# OMODRI_Power.net
KiCad netlist of a schematic drawn in Altium Designer
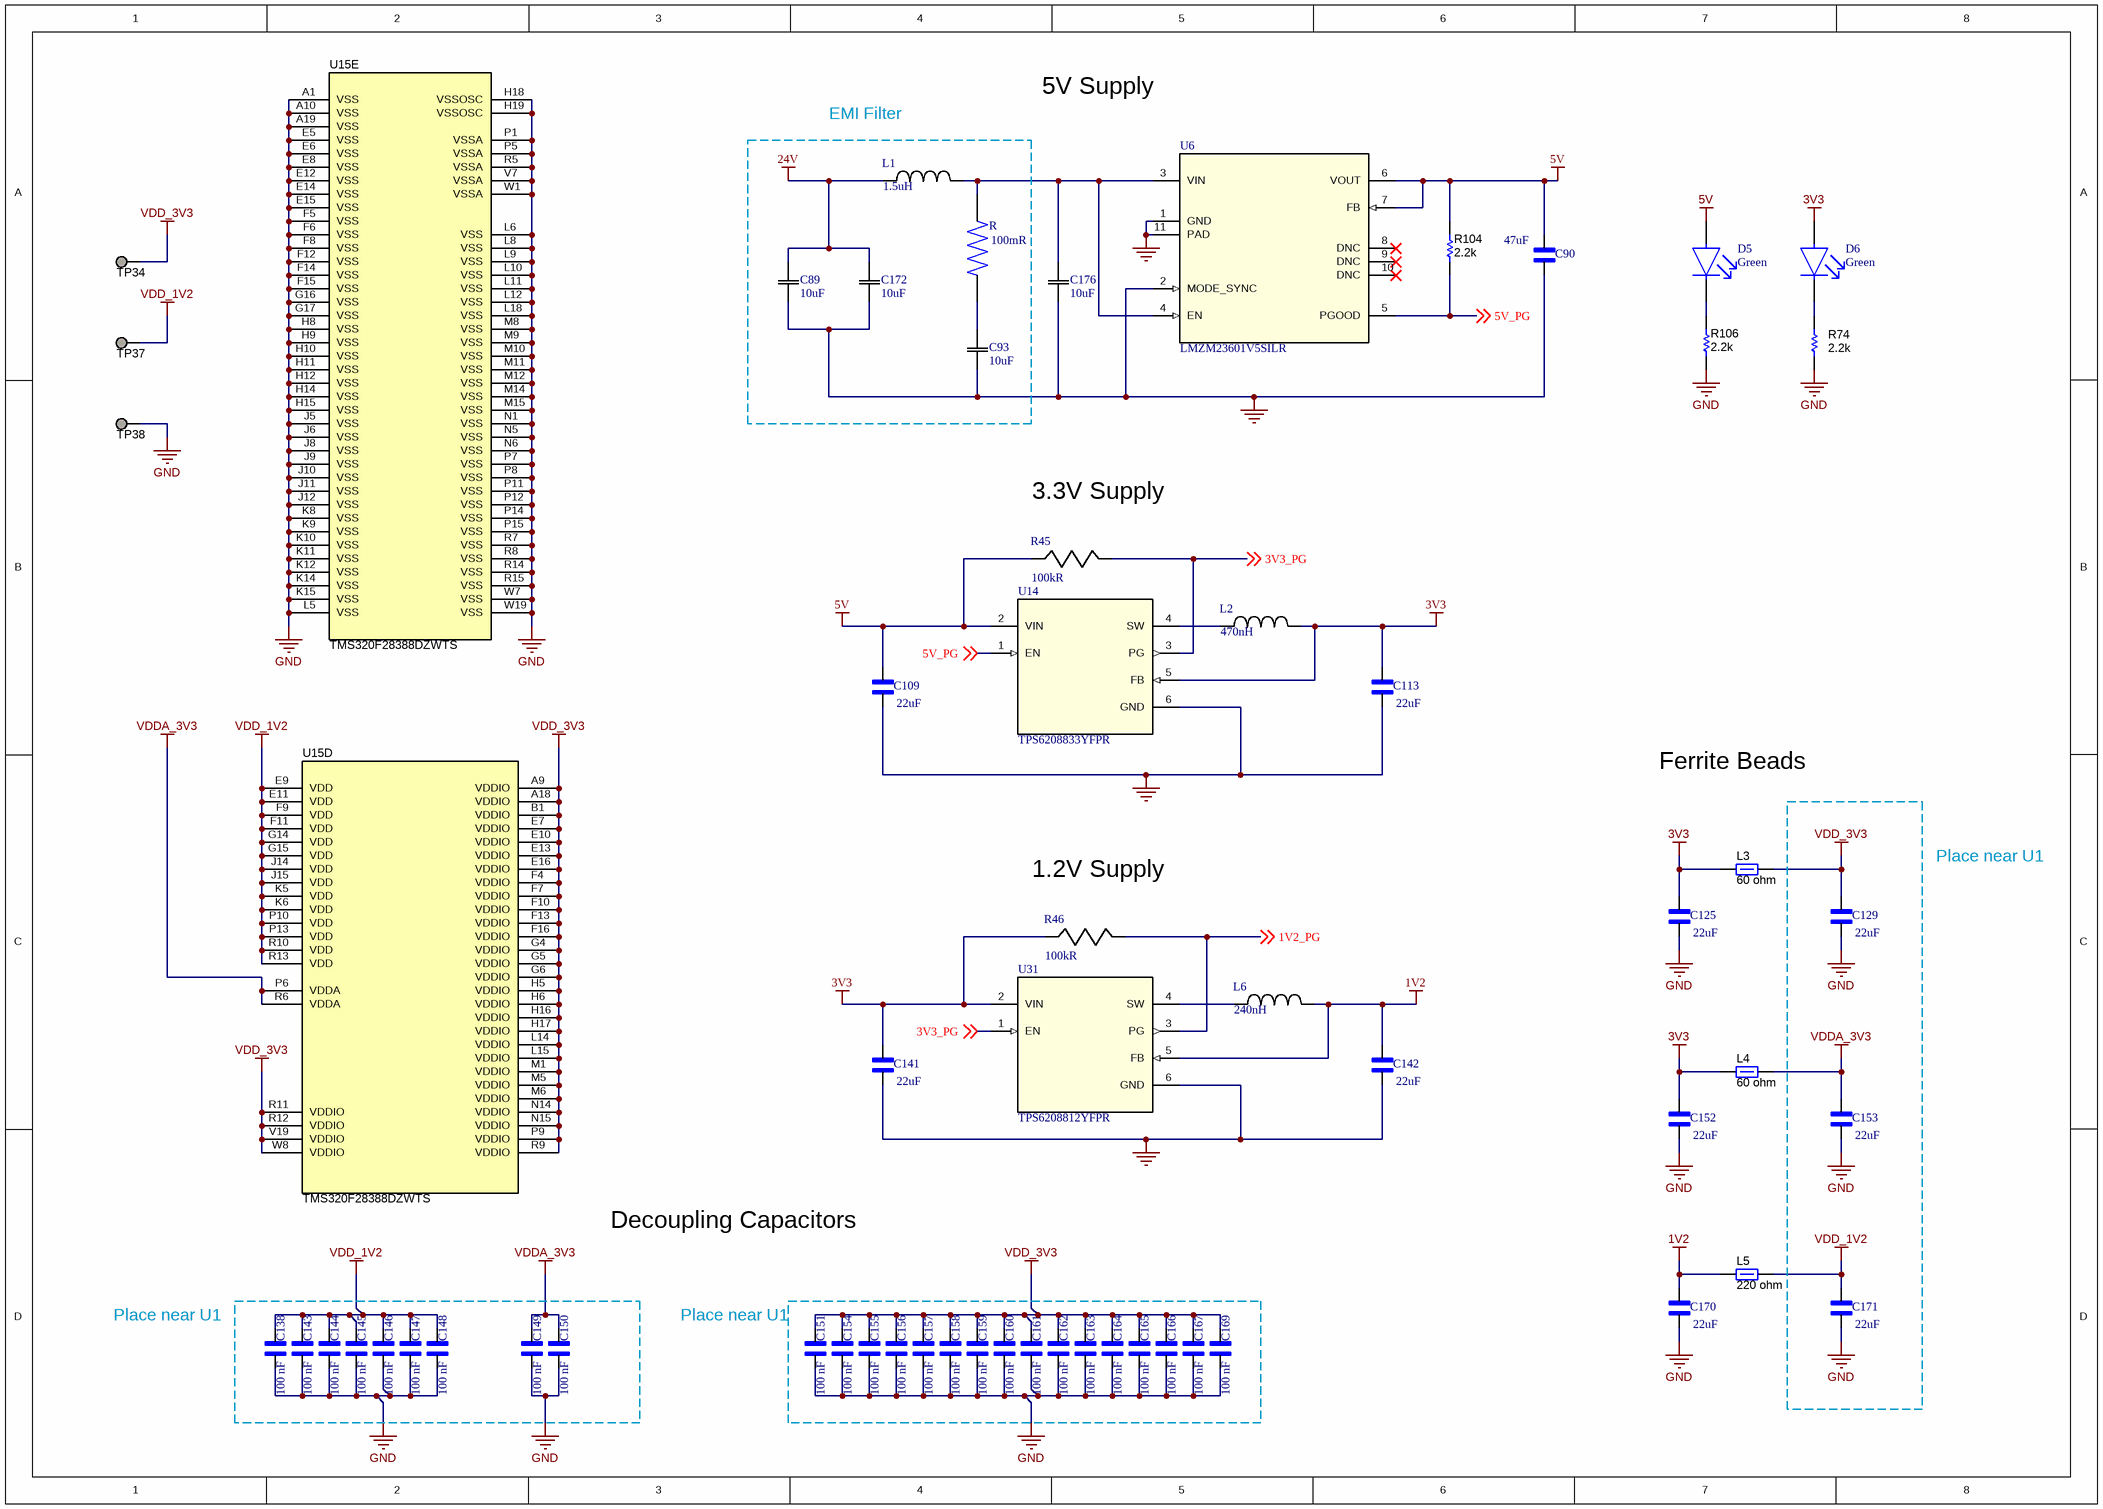
[diagram p0: OMODRI_Power.SchDoc]

(export (version "E")
  (design (tool "Eeschema 10.0.6"))
  (components
    (comp (ref "C89")
      (value "Part Number: CL10A106MA8NRNC")
      (footprint "CAP_CL10")
      (description "CAP CER 10UF 25V X5R 0603")
      (fields
        (field (name "MANUFACTURER_PART_NUMBER") "CL10A106MA8NRNC")
        (field (name "MANUFACTURER") "Samsung")
        (field (name "CAPACITANCE") "10uF")
        (field (name "COPYRIGHT") "Copyright (C) 2018 Accelerated Designs. All rights reserved")
      )
      (libsource (lib "Samsung-Capacitor") (part "CL10A106MA8NRNC"))
    )
    (comp (ref "C90")
      (value "47uF")
      (footprint "CAPC2012X145N")
      (description "47µF ±20% 10V Ceramic Capacitor X5R 0805 _2012 Metric_")
      (fields (field (name "MF") "TDK") (field (name "MP") "C2012X5R1A476M125AC"))
      (libsource (lib "C2012X5R1A476M125AC") (part "C2012X5R1A476M125AC"))
    )
    (comp (ref "C93")
      (value "Part Number: CL10A106MA8NRNC")
      (footprint "CAP_CL10")
      (description "CAP CER 10UF 25V X5R 0603")
      (fields
        (field (name "MANUFACTURER_PART_NUMBER") "CL10A106MA8NRNC")
        (field (name "MANUFACTURER") "Samsung")
        (field (name "CAPACITANCE") "10uF")
        (field (name "COPYRIGHT") "Copyright (C) 2018 Accelerated Designs. All rights reserved")
      )
      (libsource (lib "Samsung-Capacitor") (part "CL10A106MA8NRNC"))
    )
    (comp (ref "C109")
      (value "22uF")
      (footprint "CAPC1005X55N")
      (description "22µF ±20% 6.3V Ceramic Capacitor X5R 0402 (1005 Metric)")
      (fields (field (name "MP") "CL05A226MQ5N6J8") (field (name "MF") "Samsung Electro-Mechanics"))
      (libsource (lib "CL05A226MQ5N6J8") (part "CL05A226MQ5N6J8"))
    )
    (comp (ref "C113")
      (value "22uF")
      (footprint "CAPC1005X55N")
      (description "22µF ±20% 6.3V Ceramic Capacitor X5R 0402 (1005 Metric)")
      (fields (field (name "MP") "CL05A226MQ5N6J8") (field (name "MF") "Samsung Electro-Mechanics"))
      (libsource (lib "CL05A226MQ5N6J8") (part "CL05A226MQ5N6J8"))
    )
    (comp (ref "C125")
      (value "22uF")
      (footprint "CAPC1005X55N")
      (description "22µF ±20% 6.3V Ceramic Capacitor X5R 0402 (1005 Metric)")
      (fields (field (name "MP") "CL05A226MQ5N6J8") (field (name "MF") "Samsung Electro-Mechanics"))
      (libsource (lib "CL05A226MQ5N6J8") (part "CL05A226MQ5N6J8"))
    )
    (comp (ref "C129")
      (value "22uF")
      (footprint "CAPC1005X55N")
      (description "22µF ±20% 6.3V Ceramic Capacitor X5R 0402 (1005 Metric)")
      (fields (field (name "MP") "CL05A226MQ5N6J8") (field (name "MF") "Samsung Electro-Mechanics"))
      (libsource (lib "CL05A226MQ5N6J8") (part "CL05A226MQ5N6J8"))
    )
    (comp (ref "C138")
      (value "100 nF")
      (footprint "CAPC0603X33N")
      (description "SMD Capacitor X5R_EIA_ with Capacitance: 0.10uF Tol. 10%. Rated Voltage: 25Vdc")
      (fields (field (name "MF") "Murata") (field (name "MP") "GRM033R61E104KE14D"))
      (libsource (lib "GRM033R61E104KE14D") (part "GRM033R61E104KE14D"))
    )
    (comp (ref "C141")
      (value "22uF")
      (footprint "CAPC1005X55N")
      (description "22µF ±20% 6.3V Ceramic Capacitor X5R 0402 (1005 Metric)")
      (fields (field (name "MP") "CL05A226MQ5N6J8") (field (name "MF") "Samsung Electro-Mechanics"))
      (libsource (lib "CL05A226MQ5N6J8") (part "CL05A226MQ5N6J8"))
    )
    (comp (ref "C142")
      (value "22uF")
      (footprint "CAPC1005X55N")
      (description "22µF ±20% 6.3V Ceramic Capacitor X5R 0402 (1005 Metric)")
      (fields (field (name "MP") "CL05A226MQ5N6J8") (field (name "MF") "Samsung Electro-Mechanics"))
      (libsource (lib "CL05A226MQ5N6J8") (part "CL05A226MQ5N6J8"))
    )
    (comp (ref "C143")
      (value "100 nF")
      (footprint "CAPC0603X33N")
      (description "SMD Capacitor X5R_EIA_ with Capacitance: 0.10uF Tol. 10%. Rated Voltage: 25Vdc")
      (fields (field (name "MF") "Murata") (field (name "MP") "GRM033R61E104KE14D"))
      (libsource (lib "GRM033R61E104KE14D") (part "GRM033R61E104KE14D"))
    )
    (comp (ref "C144")
      (value "100 nF")
      (footprint "CAPC0603X33N")
      (description "SMD Capacitor X5R_EIA_ with Capacitance: 0.10uF Tol. 10%. Rated Voltage: 25Vdc")
      (fields (field (name "MF") "Murata") (field (name "MP") "GRM033R61E104KE14D"))
      (libsource (lib "GRM033R61E104KE14D") (part "GRM033R61E104KE14D"))
    )
    (comp (ref "C145")
      (value "100 nF")
      (footprint "CAPC0603X33N")
      (description "SMD Capacitor X5R_EIA_ with Capacitance: 0.10uF Tol. 10%. Rated Voltage: 25Vdc")
      (fields (field (name "MF") "Murata") (field (name "MP") "GRM033R61E104KE14D"))
      (libsource (lib "GRM033R61E104KE14D") (part "GRM033R61E104KE14D"))
    )
    (comp (ref "C146")
      (value "100 nF")
      (footprint "CAPC0603X33N")
      (description "SMD Capacitor X5R_EIA_ with Capacitance: 0.10uF Tol. 10%. Rated Voltage: 25Vdc")
      (fields (field (name "MF") "Murata") (field (name "MP") "GRM033R61E104KE14D"))
      (libsource (lib "GRM033R61E104KE14D") (part "GRM033R61E104KE14D"))
    )
    (comp (ref "C147")
      (value "100 nF")
      (footprint "CAPC0603X33N")
      (description "SMD Capacitor X5R_EIA_ with Capacitance: 0.10uF Tol. 10%. Rated Voltage: 25Vdc")
      (fields (field (name "MF") "Murata") (field (name "MP") "GRM033R61E104KE14D"))
      (libsource (lib "GRM033R61E104KE14D") (part "GRM033R61E104KE14D"))
    )
    (comp (ref "C148")
      (value "100 nF")
      (footprint "CAPC0603X33N")
      (description "SMD Capacitor X5R_EIA_ with Capacitance: 0.10uF Tol. 10%. Rated Voltage: 25Vdc")
      (fields (field (name "MF") "Murata") (field (name "MP") "GRM033R61E104KE14D"))
      (libsource (lib "GRM033R61E104KE14D") (part "GRM033R61E104KE14D"))
    )
    (comp (ref "C149")
      (value "100 nF")
      (footprint "CAPC0603X33N")
      (description "SMD Capacitor X5R_EIA_ with Capacitance: 0.10uF Tol. 10%. Rated Voltage: 25Vdc")
      (fields (field (name "MF") "Murata") (field (name "MP") "GRM033R61E104KE14D"))
      (libsource (lib "GRM033R61E104KE14D") (part "GRM033R61E104KE14D"))
    )
    (comp (ref "C150")
      (value "100 nF")
      (footprint "CAPC0603X33N")
      (description "SMD Capacitor X5R_EIA_ with Capacitance: 0.10uF Tol. 10%. Rated Voltage: 25Vdc")
      (fields (field (name "MF") "Murata") (field (name "MP") "GRM033R61E104KE14D"))
      (libsource (lib "GRM033R61E104KE14D") (part "GRM033R61E104KE14D"))
    )
    (comp (ref "C151")
      (value "100 nF")
      (footprint "CAPC0603X33N")
      (description "SMD Capacitor X5R_EIA_ with Capacitance: 0.10uF Tol. 10%. Rated Voltage: 25Vdc")
      (fields (field (name "MF") "Murata") (field (name "MP") "GRM033R61E104KE14D"))
      (libsource (lib "GRM033R61E104KE14D") (part "GRM033R61E104KE14D"))
    )
    (comp (ref "C152")
      (value "22uF")
      (footprint "CAPC1005X55N")
      (description "22µF ±20% 6.3V Ceramic Capacitor X5R 0402 (1005 Metric)")
      (fields (field (name "MP") "CL05A226MQ5N6J8") (field (name "MF") "Samsung Electro-Mechanics"))
      (libsource (lib "CL05A226MQ5N6J8") (part "CL05A226MQ5N6J8"))
    )
    (comp (ref "C153")
      (value "22uF")
      (footprint "CAPC1005X55N")
      (description "22µF ±20% 6.3V Ceramic Capacitor X5R 0402 (1005 Metric)")
      (fields (field (name "MP") "CL05A226MQ5N6J8") (field (name "MF") "Samsung Electro-Mechanics"))
      (libsource (lib "CL05A226MQ5N6J8") (part "CL05A226MQ5N6J8"))
    )
    (comp (ref "C154")
      (value "100 nF")
      (footprint "CAPC0603X33N")
      (description "SMD Capacitor X5R_EIA_ with Capacitance: 0.10uF Tol. 10%. Rated Voltage: 25Vdc")
      (fields (field (name "MF") "Murata") (field (name "MP") "GRM033R61E104KE14D"))
      (libsource (lib "GRM033R61E104KE14D") (part "GRM033R61E104KE14D"))
    )
    (comp (ref "C155")
      (value "100 nF")
      (footprint "CAPC0603X33N")
      (description "SMD Capacitor X5R_EIA_ with Capacitance: 0.10uF Tol. 10%. Rated Voltage: 25Vdc")
      (fields (field (name "MF") "Murata") (field (name "MP") "GRM033R61E104KE14D"))
      (libsource (lib "GRM033R61E104KE14D") (part "GRM033R61E104KE14D"))
    )
    (comp (ref "C156")
      (value "100 nF")
      (footprint "CAPC0603X33N")
      (description "SMD Capacitor X5R_EIA_ with Capacitance: 0.10uF Tol. 10%. Rated Voltage: 25Vdc")
      (fields (field (name "MF") "Murata") (field (name "MP") "GRM033R61E104KE14D"))
      (libsource (lib "GRM033R61E104KE14D") (part "GRM033R61E104KE14D"))
    )
    (comp (ref "C157")
      (value "100 nF")
      (footprint "CAPC0603X33N")
      (description "SMD Capacitor X5R_EIA_ with Capacitance: 0.10uF Tol. 10%. Rated Voltage: 25Vdc")
      (fields (field (name "MF") "Murata") (field (name "MP") "GRM033R61E104KE14D"))
      (libsource (lib "GRM033R61E104KE14D") (part "GRM033R61E104KE14D"))
    )
    (comp (ref "C158")
      (value "100 nF")
      (footprint "CAPC0603X33N")
      (description "SMD Capacitor X5R_EIA_ with Capacitance: 0.10uF Tol. 10%. Rated Voltage: 25Vdc")
      (fields (field (name "MF") "Murata") (field (name "MP") "GRM033R61E104KE14D"))
      (libsource (lib "GRM033R61E104KE14D") (part "GRM033R61E104KE14D"))
    )
    (comp (ref "C159")
      (value "100 nF")
      (footprint "CAPC0603X33N")
      (description "SMD Capacitor X5R_EIA_ with Capacitance: 0.10uF Tol. 10%. Rated Voltage: 25Vdc")
      (fields (field (name "MF") "Murata") (field (name "MP") "GRM033R61E104KE14D"))
      (libsource (lib "GRM033R61E104KE14D") (part "GRM033R61E104KE14D"))
    )
    (comp (ref "C160")
      (value "100 nF")
      (footprint "CAPC0603X33N")
      (description "SMD Capacitor X5R_EIA_ with Capacitance: 0.10uF Tol. 10%. Rated Voltage: 25Vdc")
      (fields (field (name "MF") "Murata") (field (name "MP") "GRM033R61E104KE14D"))
      (libsource (lib "GRM033R61E104KE14D") (part "GRM033R61E104KE14D"))
    )
    (comp (ref "C161")
      (value "100 nF")
      (footprint "CAPC0603X33N")
      (description "SMD Capacitor X5R_EIA_ with Capacitance: 0.10uF Tol. 10%. Rated Voltage: 25Vdc")
      (fields (field (name "MF") "Murata") (field (name "MP") "GRM033R61E104KE14D"))
      (libsource (lib "GRM033R61E104KE14D") (part "GRM033R61E104KE14D"))
    )
    (comp (ref "C162")
      (value "100 nF")
      (footprint "CAPC0603X33N")
      (description "SMD Capacitor X5R_EIA_ with Capacitance: 0.10uF Tol. 10%. Rated Voltage: 25Vdc")
      (fields (field (name "MF") "Murata") (field (name "MP") "GRM033R61E104KE14D"))
      (libsource (lib "GRM033R61E104KE14D") (part "GRM033R61E104KE14D"))
    )
    (comp (ref "C163")
      (value "100 nF")
      (footprint "CAPC0603X33N")
      (description "SMD Capacitor X5R_EIA_ with Capacitance: 0.10uF Tol. 10%. Rated Voltage: 25Vdc")
      (fields (field (name "MF") "Murata") (field (name "MP") "GRM033R61E104KE14D"))
      (libsource (lib "GRM033R61E104KE14D") (part "GRM033R61E104KE14D"))
    )
    (comp (ref "C164")
      (value "100 nF")
      (footprint "CAPC0603X33N")
      (description "SMD Capacitor X5R_EIA_ with Capacitance: 0.10uF Tol. 10%. Rated Voltage: 25Vdc")
      (fields (field (name "MF") "Murata") (field (name "MP") "GRM033R61E104KE14D"))
      (libsource (lib "GRM033R61E104KE14D") (part "GRM033R61E104KE14D"))
    )
    (comp (ref "C165")
      (value "100 nF")
      (footprint "CAPC0603X33N")
      (description "SMD Capacitor X5R_EIA_ with Capacitance: 0.10uF Tol. 10%. Rated Voltage: 25Vdc")
      (fields (field (name "MF") "Murata") (field (name "MP") "GRM033R61E104KE14D"))
      (libsource (lib "GRM033R61E104KE14D") (part "GRM033R61E104KE14D"))
    )
    (comp (ref "C166")
      (value "100 nF")
      (footprint "CAPC0603X33N")
      (description "SMD Capacitor X5R_EIA_ with Capacitance: 0.10uF Tol. 10%. Rated Voltage: 25Vdc")
      (fields (field (name "MF") "Murata") (field (name "MP") "GRM033R61E104KE14D"))
      (libsource (lib "GRM033R61E104KE14D") (part "GRM033R61E104KE14D"))
    )
    (comp (ref "C167")
      (value "100 nF")
      (footprint "CAPC0603X33N")
      (description "SMD Capacitor X5R_EIA_ with Capacitance: 0.10uF Tol. 10%. Rated Voltage: 25Vdc")
      (fields (field (name "MF") "Murata") (field (name "MP") "GRM033R61E104KE14D"))
      (libsource (lib "GRM033R61E104KE14D") (part "GRM033R61E104KE14D"))
    )
    (comp (ref "C169")
      (value "100 nF")
      (footprint "CAPC0603X33N")
      (description "SMD Capacitor X5R_EIA_ with Capacitance: 0.10uF Tol. 10%. Rated Voltage: 25Vdc")
      (fields (field (name "MF") "Murata") (field (name "MP") "GRM033R61E104KE14D"))
      (libsource (lib "GRM033R61E104KE14D") (part "GRM033R61E104KE14D"))
    )
    (comp (ref "C170")
      (value "22uF")
      (footprint "CAPC1005X55N")
      (description "22µF ±20% 6.3V Ceramic Capacitor X5R 0402 (1005 Metric)")
      (fields (field (name "MP") "CL05A226MQ5N6J8") (field (name "MF") "Samsung Electro-Mechanics"))
      (libsource (lib "CL05A226MQ5N6J8") (part "CL05A226MQ5N6J8"))
    )
    (comp (ref "C171")
      (value "22uF")
      (footprint "CAPC1005X55N")
      (description "22µF ±20% 6.3V Ceramic Capacitor X5R 0402 (1005 Metric)")
      (fields (field (name "MP") "CL05A226MQ5N6J8") (field (name "MF") "Samsung Electro-Mechanics"))
      (libsource (lib "CL05A226MQ5N6J8") (part "CL05A226MQ5N6J8"))
    )
    (comp (ref "C172")
      (value "Part Number: CL10A106MA8NRNC")
      (footprint "CAP_CL10")
      (description "CAP CER 10UF 25V X5R 0603")
      (fields
        (field (name "MANUFACTURER_PART_NUMBER") "CL10A106MA8NRNC")
        (field (name "MANUFACTURER") "Samsung")
        (field (name "CAPACITANCE") "10uF")
        (field (name "COPYRIGHT") "Copyright (C) 2018 Accelerated Designs. All rights reserved")
      )
      (libsource (lib "Samsung-Capacitor") (part "CL10A106MA8NRNC"))
    )
    (comp (ref "C176")
      (value "Part Number: CL10A106MA8NRNC")
      (footprint "CAP_CL10")
      (description "CAP CER 10UF 25V X5R 0603")
      (fields
        (field (name "MANUFACTURER_PART_NUMBER") "CL10A106MA8NRNC")
        (field (name "MANUFACTURER") "Samsung")
        (field (name "CAPACITANCE") "10uF")
        (field (name "COPYRIGHT") "Copyright (C) 2018 Accelerated Designs. All rights reserved")
      )
      (libsource (lib "Samsung-Capacitor") (part "CL10A106MA8NRNC"))
    )
    (comp (ref "D5")
      (value "SML-P11MTT86R")
      (footprint "ROHM-SML-P11MT_V")
      (description "LED Uni-Color Yellow Green 2-Pin Chip 0402(1006Metric) T/R")
      (fields
        (field (name "MANUFACTURER") "Rohm")
        (field (name "MANUFACTURER PART NUMBER") "SML-P11MTT86")
        (field (name "ILLUMINATION COLOR") "Green")
      )
      (libsource (lib "LED") (part "SML-P11MTT86R"))
    )
    (comp (ref "D6")
      (value "SML-P11MTT86R")
      (footprint "ROHM-SML-P11MT_V")
      (description "LED Uni-Color Yellow Green 2-Pin Chip 0402(1006Metric) T/R")
      (fields
        (field (name "MANUFACTURER") "Rohm")
        (field (name "MANUFACTURER PART NUMBER") "SML-P11MTT86")
        (field (name "ILLUMINATION COLOR") "Green")
      )
      (libsource (lib "LED") (part "SML-P11MTT86R"))
    )
    (comp (ref "L1")
      (value "LQM21PN1R5MC0D")
      (footprint "0805")
      (fields
        (field (name "MANUFACTURER") "Murata")
        (field (name "TOLERANCE") "20%")
        (field (name "INDUCTANCE") "1.5uH")
      )
      (libsource (lib "TI_LMZM23601V5") (part "LQM21PN1R5MC0D"))
    )
    (comp (ref "L2")
      (value "DFE18SANR47MG0L")
      (footprint "0603")
      (description "FIXED IND 470NH 2.6A 54 MOHM SMD")
      (fields
        (field (name "MANUFACTURER") "Murata")
        (field (name "TOLERANCE") "20%")
        (field (name "INDUCTANCE") "470nH")
      )
      (libsource (lib "TI_TPS_6208833") (part "DFE18SANR47MG0L"))
    )
    (comp (ref "L3")
      (value "60 ohm")
      (footprint "0805_HV")
      (description "Ferrite Bead, 60 ohm @ 100 MHz, 3 A, 0805")
      (fields
        (field (name "PARTNUMBER") "BKP2125HS600-T")
        (field (name "MANUFACTURER") "Taiyo Yuden")
        (field (name "PUBLISHER") "Texas Instruments")
      )
      (libsource (lib "Altium Vault - TI") (part "Ferrite_Bead"))
    )
    (comp (ref "L4")
      (value "60 ohm")
      (footprint "0805_HV")
      (description "Ferrite Bead, 60 ohm @ 100 MHz, 3 A, 0805")
      (fields
        (field (name "PARTNUMBER") "BKP2125HS600-T")
        (field (name "MANUFACTURER") "Taiyo Yuden")
        (field (name "PUBLISHER") "Texas Instruments")
      )
      (libsource (lib "Altium Vault - TI") (part "Ferrite_Bead"))
    )
    (comp (ref "L5")
      (value "220 ohm")
      (footprint "0805_HV")
      (description "Ferrite Bead, 220 ohm @ 100 MHz, 2 A, 0805")
      (fields
        (field (name "PARTNUMBER") "BLM21PG221SN1D")
        (field (name "MANUFACTURER") "MuRata")
        (field (name "PUBLISHER") "Texas Instruments")
      )
      (libsource (lib "Altium Vault - TI") (part "Ferrite_Bead"))
    )
    (comp (ref "L6")
      (value "DFE18SANR24ME0L")
      (footprint "DFE18_E")
      (description "FIXED IND 240NH 3.2A 36 MOHM SMD")
      (fields
        (field (name "MANUFACTURER") "Murata")
        (field (name "TOLERANCE") "20%")
        (field (name "INDUCTANCE") "240nH")
      )
      (libsource (lib "TI_TPS_6208812") (part "DFE18SANR24ME0L"))
    )
    (comp (ref "R")
      (value "100mR")
      (footprint "RESC0603X29N")
      (description "100 mOhms Â±1% 0.1W, 1/10W Chip Resistor 0201 (0603 Metric) Current Sense Thick Film")
      (fields (field (name "MF") "Rohm") (field (name "DIGI-KEY_PART_NUMBER") "RHM1694-1-ND"))
      (libsource (lib "UCR006YVPFLR100") (part "UCR006YVPFLR100"))
    )
    (comp (ref "R45")
      (value "CRCW0402100KFKED")
      (footprint "0402")
      (description "Res Thick Film 0402 100K Ohm 1% 1/16W 100ppm/C Molded SMD Paper T/R")
      (fields
        (field (name "MANUFACTURER") "Vishay")
        (field (name "TOLERANCE") "1%")
        (field (name "RESISTANCE") "100kR")
      )
      (libsource (lib "TI_TPS_6208833") (part "CRCW0402100KFKED"))
    )
    (comp (ref "R46")
      (value "CRCW0402100KFKED")
      (footprint "0402")
      (description "Res Thick Film 0402 100K Ohm 1% 1/16W 100ppm/C Molded SMD Paper T/R")
      (fields
        (field (name "MANUFACTURER") "Vishay")
        (field (name "TOLERANCE") "1%")
        (field (name "RESISTANCE") "100kR")
      )
      (libsource (lib "TI_TPS_6208833") (part "CRCW0402100KFKED"))
    )
    (comp (ref "R74")
      (value "CRCW04022K20JNED")
      (footprint "0402")
      (description "RES, 2.2 k, 5%, 0.063 W, AEC-Q200 Grade 0, 0402")
      (fields (field (name "MANUFACTURER") "Vishay-Dale") (field (name "VALUEDISPLAYED") "2.2k"))
      (libsource (lib "Altium Vault - TI") (part "Resistor"))
    )
    (comp (ref "R104")
      (value "CRCW04022K20JNED")
      (footprint "0402")
      (description "RES, 2.2 k, 5%, 0.063 W, AEC-Q200 Grade 0, 0402")
      (fields (field (name "MANUFACTURER") "Vishay-Dale") (field (name "VALUEDISPLAYED") "2.2k"))
      (libsource (lib "Altium Vault - TI") (part "Resistor"))
    )
    (comp (ref "R106")
      (value "CRCW04022K20JNED")
      (footprint "0402")
      (description "RES, 2.2 k, 5%, 0.063 W, AEC-Q200 Grade 0, 0402")
      (fields (field (name "MANUFACTURER") "Vishay-Dale") (field (name "VALUEDISPLAYED") "2.2k"))
      (libsource (lib "Altium Vault - TI") (part "Resistor"))
    )
    (comp (ref "TP34")
      (value "TESTPOINT")
      (footprint "TP_50MIL-25MILHOLE")
      (description "TEST POINT.  No entry in BOM.")
      (libsource (lib "Altium Vault - TI") (part "CMP-0078143-2"))
    )
    (comp (ref "TP37")
      (value "TESTPOINT")
      (footprint "TP_50MIL-25MILHOLE")
      (description "TEST POINT.  No entry in BOM.")
      (libsource (lib "Altium Vault - TI") (part "CMP-0078143-2"))
    )
    (comp (ref "TP38")
      (value "TESTPOINT")
      (footprint "TP_50MIL-25MILHOLE")
      (description "TEST POINT.  No entry in BOM.")
      (libsource (lib "Altium Vault - TI") (part "CMP-0078143-2"))
    )
    (comp (ref "U6")
      (value "LMZM23601V5SILR")
      (footprint "SIL0010A")
      (description "36-V, 1-A Step-Down DC-DC Power Module in 3.8-mm × 3-mm Package 10-uSiP -40 to 125")
      (fields (field (name "MANUFACTURER") "Texas Instruments"))
      (libsource (lib "TI_LMZM23601V5") (part "LMZM23601V5SILR"))
    )
    (comp (ref "U14")
      (value "TPS6208833YFPR")
      (footprint "YFP0006AAAA")
      (description "3A STEP-DOWN CONVERTER - FIXED 3")
      (fields (field (name "MANUFACTURER") "Texas Instruments"))
      (libsource (lib "TI_TPS_6208833") (part "TPS6208833YFPR"))
    )
    (comp (ref "U15")
      (value "TMS320F28388DZWTS")
      (footprint "ZWT0337A")
      (description "TMS320F28388DZWTS, ZWT0337A (NFBGA-337)")
      (fields
        (field (name "PARTNUMBER") "TMS320F28388DZWTS")
        (field (name "MANUFACTURER") "Texas Instruments")
      )
      (libsource (lib "Altium Vault - TI") (part "TMS320F28388"))
    )
    (comp (ref "U31")
      (value "TPS6208812YFPR")
      (footprint "YFP0006AAAA")
      (description "3A STEP-DOWN CONVERTER - FIXED 3")
      (fields (field (name "MANUFACTURER") "Texas Instruments"))
      (libsource (lib "TI_TPS_6208812") (part "TPS6208812YFPR"))
    )
  )
  (nets
    (net (code "1") (name "0") (class "Default")
      (node (ref "C109") (pin "1") (pinfunction "1_1") (pintype "passive"))
      (node (ref "C113") (pin "1") (pinfunction "1_1") (pintype "passive"))
      (node (ref "C141") (pin "1") (pinfunction "1_1") (pintype "passive"))
      (node (ref "C142") (pin "1") (pinfunction "1_1") (pintype "passive"))
      (node (ref "C172") (pin "1") (pinfunction "1_1") (pintype "passive"))
      (node (ref "C176") (pin "1") (pinfunction "1_1") (pintype "passive"))
      (node (ref "C89") (pin "1") (pinfunction "1_1") (pintype "passive"))
      (node (ref "C90") (pin "1") (pinfunction "1_1") (pintype "passive"))
      (node (ref "C93") (pin "1") (pinfunction "1_1") (pintype "passive"))
      (node (ref "U14") (pin "6") (pinfunction "GND_6") (pintype "power_in"))
      (node (ref "U31") (pin "6") (pinfunction "GND_6") (pintype "power_in"))
      (node (ref "U6") (pin "1") (pinfunction "GND_1") (pintype "power_in"))
      (node (ref "U6") (pin "11") (pinfunction "PAD_11") (pintype "power_in"))
      (node (ref "U6") (pin "2") (pinfunction "MODE_SYNC_2") (pintype "input"))
    )
    (net (code "2") (name "1V2") (class "Default")
      (node (ref "C142") (pin "2") (pinfunction "2_2") (pintype "passive"))
      (node (ref "C170") (pin "2") (pinfunction "2_2") (pintype "passive"))
      (node (ref "L5") (pin "1") (pinfunction "1_1") (pintype "passive"))
      (node (ref "L6") (pin "1") (pinfunction "1_1") (pintype "passive"))
      (node (ref "U31") (pin "5") (pinfunction "FB_5") (pintype "input"))
    )
    (net (code "3") (name "1V2_PG") (class "Default")
      (node (ref "R46") (pin "1") (pinfunction "1_1") (pintype "passive"))
      (node (ref "U31") (pin "3") (pinfunction "PG_3") (pintype "output"))
    )
    (net (code "4") (name "3V3") (class "Default")
      (node (ref "C113") (pin "2") (pinfunction "2_2") (pintype "passive"))
      (node (ref "C125") (pin "2") (pinfunction "2_2") (pintype "passive"))
      (node (ref "C141") (pin "2") (pinfunction "2_2") (pintype "passive"))
      (node (ref "C152") (pin "2") (pinfunction "2_2") (pintype "passive"))
      (node (ref "D6") (pin "2") (pinfunction "A_2") (pintype "passive"))
      (node (ref "L2") (pin "1") (pinfunction "1_1") (pintype "passive"))
      (node (ref "L3") (pin "1") (pinfunction "1_1") (pintype "passive"))
      (node (ref "L4") (pin "1") (pinfunction "1_1") (pintype "passive"))
      (node (ref "R46") (pin "2") (pinfunction "2_2") (pintype "passive"))
      (node (ref "U14") (pin "5") (pinfunction "FB_5") (pintype "input"))
      (node (ref "U31") (pin "2") (pinfunction "VIN_2") (pintype "power_in"))
    )
    (net (code "5") (name "3V3_PG") (class "Default")
      (node (ref "R45") (pin "1") (pinfunction "1_1") (pintype "passive"))
      (node (ref "U14") (pin "3") (pinfunction "PG_3") (pintype "output"))
      (node (ref "U31") (pin "1") (pinfunction "EN_1") (pintype "input"))
    )
    (net (code "6") (name "5V") (class "Default")
      (node (ref "C109") (pin "2") (pinfunction "2_2") (pintype "passive"))
      (node (ref "C90") (pin "2") (pinfunction "2_2") (pintype "passive"))
      (node (ref "D5") (pin "2") (pinfunction "A_2") (pintype "passive"))
      (node (ref "R104") (pin "1") (pinfunction "1_1") (pintype "passive"))
      (node (ref "R45") (pin "2") (pinfunction "2_2") (pintype "passive"))
      (node (ref "U14") (pin "2") (pinfunction "VIN_2") (pintype "power_in"))
      (node (ref "U6") (pin "6") (pinfunction "VOUT_6") (pintype "power_in"))
      (node (ref "U6") (pin "7") (pinfunction "FB_7") (pintype "input"))
    )
    (net (code "7") (name "5V_PG") (class "Default")
      (node (ref "R104") (pin "2") (pinfunction "2_2") (pintype "passive"))
      (node (ref "U14") (pin "1") (pinfunction "EN_1") (pintype "input"))
      (node (ref "U6") (pin "5") (pinfunction "PGOOD_5") (pintype "open_collector"))
    )
    (net (code "8") (name "24V") (class "Default")
      (node (ref "C172") (pin "2") (pinfunction "2_2") (pintype "passive"))
      (node (ref "C89") (pin "2") (pinfunction "2_2") (pintype "passive"))
      (node (ref "L1") (pin "1") (pinfunction "1_1") (pintype "passive"))
    )
    (net (code "9") (name "GND") (class "Default")
      (node (ref "C125") (pin "1") (pinfunction "1_1") (pintype "passive"))
      (node (ref "C129") (pin "1") (pinfunction "1_1") (pintype "passive"))
      (node (ref "C138") (pin "2") (pinfunction "2_2") (pintype "passive"))
      (node (ref "C143") (pin "2") (pinfunction "2_2") (pintype "passive"))
      (node (ref "C144") (pin "2") (pinfunction "2_2") (pintype "passive"))
      (node (ref "C145") (pin "2") (pinfunction "2_2") (pintype "passive"))
      (node (ref "C146") (pin "2") (pinfunction "2_2") (pintype "passive"))
      (node (ref "C147") (pin "2") (pinfunction "2_2") (pintype "passive"))
      (node (ref "C148") (pin "2") (pinfunction "2_2") (pintype "passive"))
      (node (ref "C149") (pin "2") (pinfunction "2_2") (pintype "passive"))
      (node (ref "C150") (pin "2") (pinfunction "2_2") (pintype "passive"))
      (node (ref "C151") (pin "2") (pinfunction "2_2") (pintype "passive"))
      (node (ref "C152") (pin "1") (pinfunction "1_1") (pintype "passive"))
      (node (ref "C153") (pin "1") (pinfunction "1_1") (pintype "passive"))
      (node (ref "C154") (pin "2") (pinfunction "2_2") (pintype "passive"))
      (node (ref "C155") (pin "2") (pinfunction "2_2") (pintype "passive"))
      (node (ref "C156") (pin "2") (pinfunction "2_2") (pintype "passive"))
      (node (ref "C157") (pin "2") (pinfunction "2_2") (pintype "passive"))
      (node (ref "C158") (pin "2") (pinfunction "2_2") (pintype "passive"))
      (node (ref "C159") (pin "2") (pinfunction "2_2") (pintype "passive"))
      (node (ref "C160") (pin "2") (pinfunction "2_2") (pintype "passive"))
      (node (ref "C161") (pin "2") (pinfunction "2_2") (pintype "passive"))
      (node (ref "C162") (pin "2") (pinfunction "2_2") (pintype "passive"))
      (node (ref "C163") (pin "2") (pinfunction "2_2") (pintype "passive"))
      (node (ref "C164") (pin "2") (pinfunction "2_2") (pintype "passive"))
      (node (ref "C165") (pin "2") (pinfunction "2_2") (pintype "passive"))
      (node (ref "C166") (pin "2") (pinfunction "2_2") (pintype "passive"))
      (node (ref "C167") (pin "2") (pinfunction "2_2") (pintype "passive"))
      (node (ref "C169") (pin "2") (pinfunction "2_2") (pintype "passive"))
      (node (ref "C170") (pin "1") (pinfunction "1_1") (pintype "passive"))
      (node (ref "C171") (pin "1") (pinfunction "1_1") (pintype "passive"))
      (node (ref "R106") (pin "2") (pinfunction "2_2") (pintype "passive"))
      (node (ref "R74") (pin "1") (pinfunction "1_1") (pintype "passive"))
      (node (ref "TP38") (pin "1") (pintype "passive"))
      (node (ref "U15") (pin "A1") (pinfunction "VSS_A1") (pintype "power_in"))
      (node (ref "U15") (pin "A10") (pinfunction "VSS_A10") (pintype "power_in"))
      (node (ref "U15") (pin "A19") (pinfunction "VSS_A19") (pintype "power_in"))
      (node (ref "U15") (pin "E12") (pinfunction "VSS_E12") (pintype "power_in"))
      (node (ref "U15") (pin "E14") (pinfunction "VSS_E14") (pintype "power_in"))
      (node (ref "U15") (pin "E15") (pinfunction "VSS_E15") (pintype "power_in"))
      (node (ref "U15") (pin "E5") (pinfunction "VSS_E5") (pintype "power_in"))
      (node (ref "U15") (pin "E6") (pinfunction "VSS_E6") (pintype "power_in"))
      (node (ref "U15") (pin "E8") (pinfunction "VSS_E8") (pintype "power_in"))
      (node (ref "U15") (pin "F12") (pinfunction "VSS_F12") (pintype "power_in"))
      (node (ref "U15") (pin "F14") (pinfunction "VSS_F14") (pintype "power_in"))
      (node (ref "U15") (pin "F15") (pinfunction "VSS_F15") (pintype "power_in"))
      (node (ref "U15") (pin "F5") (pinfunction "VSS_F5") (pintype "power_in"))
      (node (ref "U15") (pin "F6") (pinfunction "VSS_F6") (pintype "power_in"))
      (node (ref "U15") (pin "F8") (pinfunction "VSS_F8") (pintype "power_in"))
      (node (ref "U15") (pin "G16") (pinfunction "VSS_G16") (pintype "power_in"))
      (node (ref "U15") (pin "G17") (pinfunction "VSS_G17") (pintype "power_in"))
      (node (ref "U15") (pin "H10") (pinfunction "VSS_H10") (pintype "power_in"))
      (node (ref "U15") (pin "H11") (pinfunction "VSS_H11") (pintype "power_in"))
      (node (ref "U15") (pin "H12") (pinfunction "VSS_H12") (pintype "power_in"))
      (node (ref "U15") (pin "H14") (pinfunction "VSS_H14") (pintype "power_in"))
      (node (ref "U15") (pin "H15") (pinfunction "VSS_H15") (pintype "power_in"))
      (node (ref "U15") (pin "H18") (pinfunction "VSSOSC_H18") (pintype "power_in"))
      (node (ref "U15") (pin "H19") (pinfunction "VSSOSC_H19") (pintype "power_in"))
      (node (ref "U15") (pin "H8") (pinfunction "VSS_H8") (pintype "power_in"))
      (node (ref "U15") (pin "H9") (pinfunction "VSS_H9") (pintype "power_in"))
      (node (ref "U15") (pin "J10") (pinfunction "VSS_J10") (pintype "power_in"))
      (node (ref "U15") (pin "J11") (pinfunction "VSS_J11") (pintype "power_in"))
      (node (ref "U15") (pin "J12") (pinfunction "VSS_J12") (pintype "power_in"))
      (node (ref "U15") (pin "J5") (pinfunction "VSS_J5") (pintype "power_in"))
      (node (ref "U15") (pin "J6") (pinfunction "VSS_J6") (pintype "power_in"))
      (node (ref "U15") (pin "J8") (pinfunction "VSS_J8") (pintype "power_in"))
      (node (ref "U15") (pin "J9") (pinfunction "VSS_J9") (pintype "power_in"))
      (node (ref "U15") (pin "K10") (pinfunction "VSS_K10") (pintype "power_in"))
      (node (ref "U15") (pin "K11") (pinfunction "VSS_K11") (pintype "power_in"))
      (node (ref "U15") (pin "K12") (pinfunction "VSS_K12") (pintype "power_in"))
      (node (ref "U15") (pin "K14") (pinfunction "VSS_K14") (pintype "power_in"))
      (node (ref "U15") (pin "K15") (pinfunction "VSS_K15") (pintype "power_in"))
      (node (ref "U15") (pin "K8") (pinfunction "VSS_K8") (pintype "power_in"))
      (node (ref "U15") (pin "K9") (pinfunction "VSS_K9") (pintype "power_in"))
      (node (ref "U15") (pin "L10") (pinfunction "VSS_L10") (pintype "power_in"))
      (node (ref "U15") (pin "L11") (pinfunction "VSS_L11") (pintype "power_in"))
      (node (ref "U15") (pin "L12") (pinfunction "VSS_L12") (pintype "power_in"))
      (node (ref "U15") (pin "L18") (pinfunction "VSS_L18") (pintype "power_in"))
      (node (ref "U15") (pin "L5") (pinfunction "VSS_L5") (pintype "power_in"))
      (node (ref "U15") (pin "L6") (pinfunction "VSS_L6") (pintype "power_in"))
      (node (ref "U15") (pin "L8") (pinfunction "VSS_L8") (pintype "power_in"))
      (node (ref "U15") (pin "L9") (pinfunction "VSS_L9") (pintype "power_in"))
      (node (ref "U15") (pin "M10") (pinfunction "VSS_M10") (pintype "power_in"))
      (node (ref "U15") (pin "M11") (pinfunction "VSS_M11") (pintype "power_in"))
      (node (ref "U15") (pin "M12") (pinfunction "VSS_M12") (pintype "power_in"))
      (node (ref "U15") (pin "M14") (pinfunction "VSS_M14") (pintype "power_in"))
      (node (ref "U15") (pin "M15") (pinfunction "VSS_M15") (pintype "power_in"))
      (node (ref "U15") (pin "M8") (pinfunction "VSS_M8") (pintype "power_in"))
      (node (ref "U15") (pin "M9") (pinfunction "VSS_M9") (pintype "power_in"))
      (node (ref "U15") (pin "N1") (pinfunction "VSS_N1") (pintype "power_in"))
      (node (ref "U15") (pin "N5") (pinfunction "VSS_N5") (pintype "power_in"))
      (node (ref "U15") (pin "N6") (pinfunction "VSS_N6") (pintype "power_in"))
      (node (ref "U15") (pin "P1") (pinfunction "VSSA_P1") (pintype "power_in"))
      (node (ref "U15") (pin "P11") (pinfunction "VSS_P11") (pintype "power_in"))
      (node (ref "U15") (pin "P12") (pinfunction "VSS_P12") (pintype "power_in"))
      (node (ref "U15") (pin "P14") (pinfunction "VSS_P14") (pintype "power_in"))
      (node (ref "U15") (pin "P15") (pinfunction "VSS_P15") (pintype "power_in"))
      (node (ref "U15") (pin "P5") (pinfunction "VSSA_P5") (pintype "power_in"))
      (node (ref "U15") (pin "P7") (pinfunction "VSS_P7") (pintype "power_in"))
      (node (ref "U15") (pin "P8") (pinfunction "VSS_P8") (pintype "power_in"))
      (node (ref "U15") (pin "R14") (pinfunction "VSS_R14") (pintype "power_in"))
      (node (ref "U15") (pin "R15") (pinfunction "VSS_R15") (pintype "power_in"))
      (node (ref "U15") (pin "R5") (pinfunction "VSSA_R5") (pintype "power_in"))
      (node (ref "U15") (pin "R7") (pinfunction "VSS_R7") (pintype "power_in"))
      (node (ref "U15") (pin "R8") (pinfunction "VSS_R8") (pintype "power_in"))
      (node (ref "U15") (pin "V7") (pinfunction "VSSA_V7") (pintype "power_in"))
      (node (ref "U15") (pin "W1") (pinfunction "VSSA_W1") (pintype "power_in"))
      (node (ref "U15") (pin "W19") (pinfunction "VSS_W19") (pintype "power_in"))
      (node (ref "U15") (pin "W7") (pinfunction "VSS_W7") (pintype "power_in"))
    )
    (net (code "10") (name "Net-(C93-Pad2)") (class "Default")
      (node (ref "C93") (pin "2") (pinfunction "2_2") (pintype "passive"))
      (node (ref "R") (pin "1") (pinfunction "1_1") (pintype "passive"))
    )
    (net (code "11") (name "Net-(D5-C)") (class "Default")
      (node (ref "D5") (pin "1") (pinfunction "C_1") (pintype "passive"))
      (node (ref "R106") (pin "1") (pinfunction "1_1") (pintype "passive"))
    )
    (net (code "12") (name "Net-(D6-C)") (class "Default")
      (node (ref "D6") (pin "1") (pinfunction "C_1") (pintype "passive"))
      (node (ref "R74") (pin "2") (pinfunction "2_2") (pintype "passive"))
    )
    (net (code "13") (name "Net-(U6-EN)") (class "Default")
      (node (ref "C176") (pin "2") (pinfunction "2_2") (pintype "passive"))
      (node (ref "L1") (pin "2") (pinfunction "2_2") (pintype "passive"))
      (node (ref "R") (pin "2") (pinfunction "2_2") (pintype "passive"))
      (node (ref "U6") (pin "3") (pinfunction "VIN_3") (pintype "power_in"))
      (node (ref "U6") (pin "4") (pinfunction "EN_4") (pintype "input"))
    )
    (net (code "14") (name "Net-(U14-SW)") (class "Default")
      (node (ref "L2") (pin "2") (pinfunction "2_2") (pintype "passive"))
      (node (ref "U14") (pin "4") (pinfunction "SW_4") (pintype "passive"))
    )
    (net (code "15") (name "Net-(U31-SW)") (class "Default")
      (node (ref "L6") (pin "2") (pinfunction "2_2") (pintype "passive"))
      (node (ref "U31") (pin "4") (pinfunction "SW_4") (pintype "passive"))
    )
    (net (code "16") (name "VDDA_3V3") (class "Default")
      (node (ref "C149") (pin "1") (pinfunction "1_1") (pintype "passive"))
      (node (ref "C150") (pin "1") (pinfunction "1_1") (pintype "passive"))
      (node (ref "C153") (pin "2") (pinfunction "2_2") (pintype "passive"))
      (node (ref "L4") (pin "2") (pinfunction "2_2") (pintype "passive"))
      (node (ref "U15") (pin "P6") (pinfunction "VDDA_P6") (pintype "power_in"))
      (node (ref "U15") (pin "R6") (pinfunction "VDDA_R6") (pintype "power_in"))
    )
    (net (code "17") (name "VDD_1V2") (class "Default")
      (node (ref "C138") (pin "1") (pinfunction "1_1") (pintype "passive"))
      (node (ref "C143") (pin "1") (pinfunction "1_1") (pintype "passive"))
      (node (ref "C144") (pin "1") (pinfunction "1_1") (pintype "passive"))
      (node (ref "C145") (pin "1") (pinfunction "1_1") (pintype "passive"))
      (node (ref "C146") (pin "1") (pinfunction "1_1") (pintype "passive"))
      (node (ref "C147") (pin "1") (pinfunction "1_1") (pintype "passive"))
      (node (ref "C148") (pin "1") (pinfunction "1_1") (pintype "passive"))
      (node (ref "C171") (pin "2") (pinfunction "2_2") (pintype "passive"))
      (node (ref "L5") (pin "2") (pinfunction "2_2") (pintype "passive"))
      (node (ref "TP37") (pin "1") (pintype "passive"))
      (node (ref "U15") (pin "E11") (pinfunction "VDD_E11") (pintype "power_in"))
      (node (ref "U15") (pin "E9") (pinfunction "VDD_E9") (pintype "power_in"))
      (node (ref "U15") (pin "F11") (pinfunction "VDD_F11") (pintype "power_in"))
      (node (ref "U15") (pin "F9") (pinfunction "VDD_F9") (pintype "power_in"))
      (node (ref "U15") (pin "G14") (pinfunction "VDD_G14") (pintype "power_in"))
      (node (ref "U15") (pin "G15") (pinfunction "VDD_G15") (pintype "power_in"))
      (node (ref "U15") (pin "J14") (pinfunction "VDD_J14") (pintype "power_in"))
      (node (ref "U15") (pin "J15") (pinfunction "VDD_J15") (pintype "power_in"))
      (node (ref "U15") (pin "K5") (pinfunction "VDD_K5") (pintype "power_in"))
      (node (ref "U15") (pin "K6") (pinfunction "VDD_K6") (pintype "power_in"))
      (node (ref "U15") (pin "P10") (pinfunction "VDD_P10") (pintype "power_in"))
      (node (ref "U15") (pin "P13") (pinfunction "VDD_P13") (pintype "power_in"))
      (node (ref "U15") (pin "R10") (pinfunction "VDD_R10") (pintype "power_in"))
      (node (ref "U15") (pin "R13") (pinfunction "VDD_R13") (pintype "power_in"))
    )
    (net (code "18") (name "VDD_3V3") (class "Default")
      (node (ref "C129") (pin "2") (pinfunction "2_2") (pintype "passive"))
      (node (ref "C151") (pin "1") (pinfunction "1_1") (pintype "passive"))
      (node (ref "C154") (pin "1") (pinfunction "1_1") (pintype "passive"))
      (node (ref "C155") (pin "1") (pinfunction "1_1") (pintype "passive"))
      (node (ref "C156") (pin "1") (pinfunction "1_1") (pintype "passive"))
      (node (ref "C157") (pin "1") (pinfunction "1_1") (pintype "passive"))
      (node (ref "C158") (pin "1") (pinfunction "1_1") (pintype "passive"))
      (node (ref "C159") (pin "1") (pinfunction "1_1") (pintype "passive"))
      (node (ref "C160") (pin "1") (pinfunction "1_1") (pintype "passive"))
      (node (ref "C161") (pin "1") (pinfunction "1_1") (pintype "passive"))
      (node (ref "C162") (pin "1") (pinfunction "1_1") (pintype "passive"))
      (node (ref "C163") (pin "1") (pinfunction "1_1") (pintype "passive"))
      (node (ref "C164") (pin "1") (pinfunction "1_1") (pintype "passive"))
      (node (ref "C165") (pin "1") (pinfunction "1_1") (pintype "passive"))
      (node (ref "C166") (pin "1") (pinfunction "1_1") (pintype "passive"))
      (node (ref "C167") (pin "1") (pinfunction "1_1") (pintype "passive"))
      (node (ref "C169") (pin "1") (pinfunction "1_1") (pintype "passive"))
      (node (ref "L3") (pin "2") (pinfunction "2_2") (pintype "passive"))
      (node (ref "TP34") (pin "1") (pintype "passive"))
      (node (ref "U15") (pin "A18") (pinfunction "VDDIO_A18") (pintype "power_in"))
      (node (ref "U15") (pin "A9") (pinfunction "VDDIO_A9") (pintype "power_in"))
      (node (ref "U15") (pin "B1") (pinfunction "VDDIO_B1") (pintype "power_in"))
      (node (ref "U15") (pin "E10") (pinfunction "VDDIO_E10") (pintype "power_in"))
      (node (ref "U15") (pin "E13") (pinfunction "VDDIO_E13") (pintype "power_in"))
      (node (ref "U15") (pin "E16") (pinfunction "VDDIO_E16") (pintype "power_in"))
      (node (ref "U15") (pin "E7") (pinfunction "VDDIO_E7") (pintype "power_in"))
      (node (ref "U15") (pin "F10") (pinfunction "VDDIO_F10") (pintype "power_in"))
      (node (ref "U15") (pin "F13") (pinfunction "VDDIO_F13") (pintype "power_in"))
      (node (ref "U15") (pin "F16") (pinfunction "VDDIO_F16") (pintype "power_in"))
      (node (ref "U15") (pin "F4") (pinfunction "VDDIO_F4") (pintype "power_in"))
      (node (ref "U15") (pin "F7") (pinfunction "VDDIO_F7") (pintype "power_in"))
      (node (ref "U15") (pin "G4") (pinfunction "VDDIO_G4") (pintype "power_in"))
      (node (ref "U15") (pin "G5") (pinfunction "VDDIO_G5") (pintype "power_in"))
      (node (ref "U15") (pin "G6") (pinfunction "VDDIO_G6") (pintype "power_in"))
      (node (ref "U15") (pin "H16") (pinfunction "VDDIO_H16") (pintype "power_in"))
      (node (ref "U15") (pin "H17") (pinfunction "VDDIO_H17") (pintype "power_in"))
      (node (ref "U15") (pin "H5") (pinfunction "VDDIO_H5") (pintype "power_in"))
      (node (ref "U15") (pin "H6") (pinfunction "VDDIO_H6") (pintype "power_in"))
      (node (ref "U15") (pin "L14") (pinfunction "VDDIO_L14") (pintype "power_in"))
      (node (ref "U15") (pin "L15") (pinfunction "VDDIO_L15") (pintype "power_in"))
      (node (ref "U15") (pin "M1") (pinfunction "VDDIO_M1") (pintype "power_in"))
      (node (ref "U15") (pin "M5") (pinfunction "VDDIO_M5") (pintype "power_in"))
      (node (ref "U15") (pin "M6") (pinfunction "VDDIO_M6") (pintype "power_in"))
      (node (ref "U15") (pin "N14") (pinfunction "VDDIO_N14") (pintype "power_in"))
      (node (ref "U15") (pin "N15") (pinfunction "VDDIO_N15") (pintype "power_in"))
      (node (ref "U15") (pin "P9") (pinfunction "VDDIO_P9") (pintype "power_in"))
      (node (ref "U15") (pin "R11") (pinfunction "VDDIO_R11") (pintype "power_in"))
      (node (ref "U15") (pin "R12") (pinfunction "VDDIO_R12") (pintype "power_in"))
      (node (ref "U15") (pin "R9") (pinfunction "VDDIO_R9") (pintype "power_in"))
      (node (ref "U15") (pin "V19") (pinfunction "VDDIO_V19") (pintype "power_in"))
      (node (ref "U15") (pin "W8") (pinfunction "VDDIO_W8") (pintype "power_in"))
    )
    (net (code "19") (name "unconnected-(U6-DNC-Pad8)") (class "Default")
      (node (ref "U6") (pin "8") (pinfunction "DNC_8") (pintype "passive+no_connect"))
    )
    (net (code "20") (name "unconnected-(U6-DNC-Pad9)") (class "Default")
      (node (ref "U6") (pin "9") (pinfunction "DNC_9") (pintype "passive+no_connect"))
    )
    (net (code "21") (name "unconnected-(U6-DNC-Pad10)") (class "Default")
      (node (ref "U6") (pin "10") (pinfunction "DNC_10") (pintype "passive+no_connect"))
    )
  )
)
